# led_frontend.net
KiCad netlist of a schematic drawn in Altium Designer
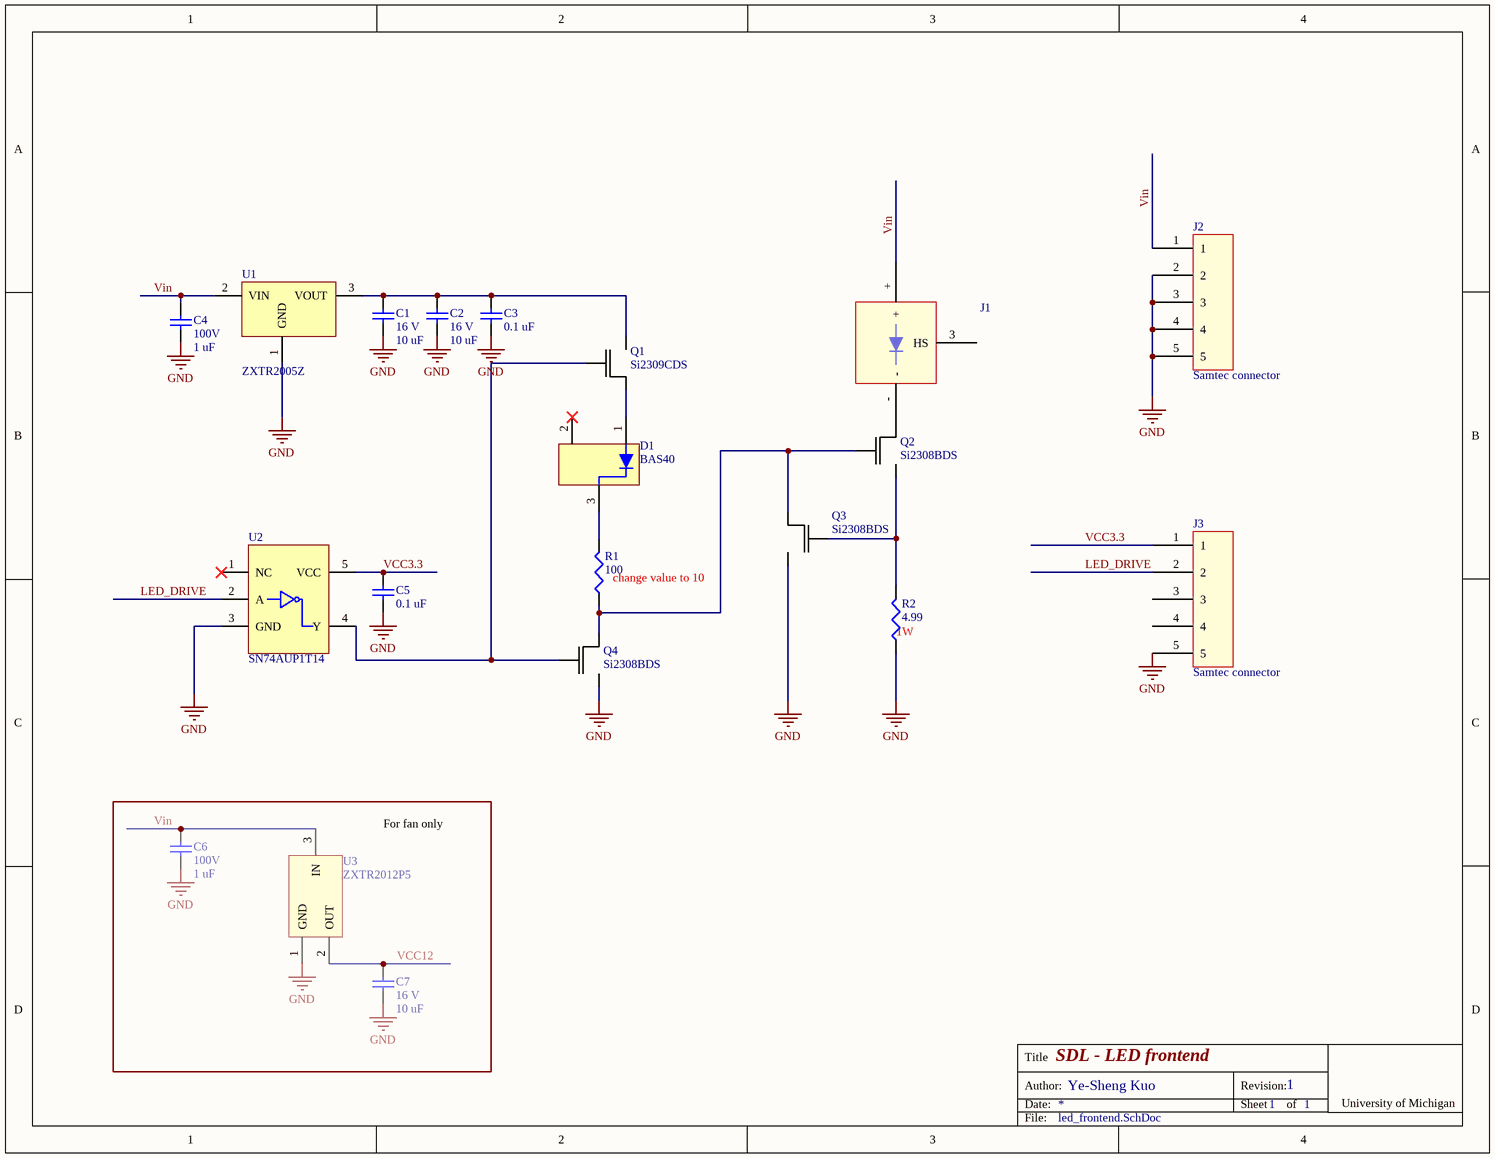
[diagram p0: led_frontend.SchDoc]

(export (version "E")
  (design (tool "Eeschema 10.0.6"))
  (components
    (comp (ref "C1")
      (value "10 uF")
      (footprint "0603")
      (description "Ceramic capacitor, 10 uF, 16 V, 0603 package")
      (fields
        (field (name "TOLERANCE") "20%")
        (field (name "VOLTAGE RATED") "16 V")
        (field (name "Comment") "Ceramic capacitor")
      )
      (libsource (lib "rlc") (part "C_10u_16V_0603_ceramic"))
    )
    (comp (ref "C2")
      (value "10 uF")
      (footprint "0603")
      (description "Ceramic capacitor, 10 uF, 16 V, 0603 package")
      (fields
        (field (name "TOLERANCE") "20%")
        (field (name "VOLTAGE RATED") "16 V")
        (field (name "Comment") "Ceramic capacitor")
      )
      (libsource (lib "rlc") (part "C_10u_16V_0603_ceramic"))
    )
    (comp (ref "C3")
      (value "0.1 uF")
      (footprint "0603")
      (description "Ceramic capacitor, 0.1 uF, 0603 package")
      (fields (field (name "TOLERANCE") "10%") (field (name "Comment") "Ceramic capacitor"))
      (libsource (lib "rlc") (part "C_0.1u_0603_ceramic"))
    )
    (comp (ref "C4")
      (value "1 uF")
      (footprint "0805")
      (description "Ceramic capacitor, 1 uF, 100 V, 0805 package")
      (fields
        (field (name "TOLERANCE") "10%")
        (field (name "VOLTAGE RATED") "100V")
        (field (name "Comment") "Ceramic capacitor")
      )
      (libsource (lib "rlc") (part "C_1u_100V_0805_ceramic"))
    )
    (comp (ref "C5")
      (value "0.1 uF")
      (footprint "0603")
      (description "Ceramic capacitor, 0.1 uF, 0603 package")
      (fields (field (name "TOLERANCE") "10%") (field (name "Comment") "Ceramic capacitor"))
      (libsource (lib "rlc") (part "C_0.1u_0603_ceramic"))
    )
    (comp (ref "C6")
      (value "1 uF")
      (footprint "0805")
      (description "Ceramic capacitor, 1 uF, 100 V, 0805 package")
      (fields
        (field (name "TOLERANCE") "10%")
        (field (name "VOLTAGE RATED") "100V")
        (field (name "Comment") "Ceramic capacitor")
      )
      (libsource (lib "rlc") (part "C_1u_100V_0805_ceramic"))
    )
    (comp (ref "C7")
      (value "10 uF")
      (footprint "0603")
      (description "Ceramic capacitor, 10 uF, 16 V, 0603 package")
      (fields
        (field (name "TOLERANCE") "20%")
        (field (name "VOLTAGE RATED") "16 V")
        (field (name "Comment") "Ceramic capacitor")
      )
      (libsource (lib "rlc") (part "C_10u_16V_0603_ceramic"))
    )
    (comp (ref "D1")
      (value "BAS40")
      (footprint "SOT23-3")
      (description "SURFACE MOUNT SCHOTTKY BARRIER DIODE")
      (libsource (lib "sdl") (part "BAS40"))
    )
    (comp (ref "J1")
      (value "1807200002")
      (footprint "molex")
      (description "LED Array Holders  for CREE* XLamp†   Arrays")
      (libsource (lib "connectors") (part "Molex LED holder"))
    )
    (comp (ref "J2")
      (value "Samtec connector")
      (footprint "TFM-105-02-L-S")
      (description "Samtec connector, 1.27 mm, single row, 5 pos SMD")
      (libsource (lib "connectors") (part "Samtec conntector"))
    )
    (comp (ref "J3")
      (value "Samtec connector")
      (footprint "TFM-105-02-L-S")
      (description "Samtec connector, 1.27 mm, single row, 5 pos SMD")
      (libsource (lib "connectors") (part "Samtec conntector"))
    )
    (comp (ref "Q1")
      (value "Si2309CDS")
      (footprint "SOT23-3")
      (description "P-Channel 60-V (D-S) MOSFET")
      (libsource (lib "transistors") (part "Si2309CDS"))
    )
    (comp (ref "Q2")
      (value "Si2308BDS")
      (footprint "SOT23-3")
      (description "N-Channel 60-V (D-S) MOSFET")
      (libsource (lib "transistors") (part "Si2308BDS"))
    )
    (comp (ref "Q3")
      (value "Si2308BDS")
      (footprint "SOT23-3")
      (description "N-Channel 60-V (D-S) MOSFET")
      (libsource (lib "transistors") (part "Si2308BDS"))
    )
    (comp (ref "Q4")
      (value "Si2308BDS")
      (footprint "SOT23-3")
      (description "N-Channel 60-V (D-S) MOSFET")
      (libsource (lib "transistors") (part "Si2308BDS"))
    )
    (comp (ref "R1")
      (value "100")
      (footprint "0603")
      (description "Chip resistor, 100,  0603 package")
      (fields (field (name "TOLERANCE") "0.1%") (field (name "POWER") "1/1 W"))
      (libsource (lib "rlc") (part "R_100_0603"))
    )
    (comp (ref "R2")
      (value "4.99")
      (footprint "2512")
      (description "Chip resistor, 4.99, 2512 package")
      (fields (field (name "TOLERANCE") "1%") (field (name "POWER") "1 W"))
      (libsource (lib "rlc") (part "R_4.99_2512"))
    )
    (comp (ref "U1")
      (value "ZXTR2005Z")
      (footprint "SOT89")
      (description "100V INPUT, 5V 30mA REGULATOR TRANSISTOR")
      (libsource (lib "ldo") (part "ZXTR2005Z"))
    )
    (comp (ref "U2")
      (value "SN74AUP1T14")
      (footprint "SC-70-5 (DCK)")
      (description "LOW POWER, 1.8/2.5/3.3-V INPUT, 3.3-V CMOS OUTPUT, SINGLE  SCHMITT-TRIGGER INVERTER GATE")
      (libsource (lib "sdl") (part "SN74AUP1T14"))
    )
    (comp (ref "U3")
      (value "ZXTR2012P5")
      (footprint "PowerDI-5")
      (description "100V INPUT, 12V 40mA REGULATOR TRANSISTOR")
      (libsource (lib "ldo") (part "ZXTR2012P5"))
    )
  )
  (nets
    (net (code "1") (name "/LED_DRIVE") (class "Default")
      (node (ref "J3") (pin "2") (pinfunction "2_2") (pintype "passive"))
      (node (ref "U2") (pin "2") (pinfunction "A_2") (pintype "power_in"))
    )
    (net (code "2") (name "/VCC3.3") (class "Default")
      (node (ref "C5") (pin "1") (pintype "passive"))
      (node (ref "J3") (pin "1") (pinfunction "1_1") (pintype "passive"))
      (node (ref "U2") (pin "5") (pinfunction "VCC_5") (pintype "power_in"))
    )
    (net (code "3") (name "/VCC12") (class "Default")
      (node (ref "C7") (pin "1") (pintype "passive"))
      (node (ref "U3") (pin "2") (pinfunction "OUT_2") (pintype "passive"))
    )
    (net (code "4") (name "/Vin") (class "Default")
      (node (ref "C4") (pin "1") (pintype "passive"))
      (node (ref "C6") (pin "1") (pintype "passive"))
      (node (ref "J1") (pin "+") (pinfunction "+_+") (pintype "passive"))
      (node (ref "J2") (pin "1") (pinfunction "1_1") (pintype "passive"))
      (node (ref "U1") (pin "2") (pinfunction "VIN_2") (pintype "passive"))
      (node (ref "U3") (pin "3") (pinfunction "IN_3") (pintype "passive"))
    )
    (net (code "5") (name "GND") (class "Default")
      (node (ref "C1") (pin "2") (pintype "passive"))
      (node (ref "C2") (pin "2") (pintype "passive"))
      (node (ref "C3") (pin "2") (pintype "passive"))
      (node (ref "C4") (pin "2") (pintype "passive"))
      (node (ref "C5") (pin "2") (pintype "passive"))
      (node (ref "C6") (pin "2") (pintype "passive"))
      (node (ref "C7") (pin "2") (pintype "passive"))
      (node (ref "J2") (pin "2") (pinfunction "2_2") (pintype "passive"))
      (node (ref "J2") (pin "3") (pinfunction "3_3") (pintype "passive"))
      (node (ref "J2") (pin "4") (pinfunction "4_4") (pintype "passive"))
      (node (ref "J2") (pin "5") (pinfunction "5_5") (pintype "passive"))
      (node (ref "J3") (pin "5") (pinfunction "5_5") (pintype "passive"))
      (node (ref "Q3") (pin "2") (pinfunction "S_2") (pintype "passive"))
      (node (ref "Q4") (pin "2") (pinfunction "S_2") (pintype "passive"))
      (node (ref "R2") (pin "2") (pintype "passive"))
      (node (ref "U1") (pin "1") (pinfunction "GND_1") (pintype "passive"))
      (node (ref "U2") (pin "3") (pinfunction "GND_3") (pintype "power_in"))
      (node (ref "U3") (pin "1") (pinfunction "GND_1") (pintype "passive"))
    )
    (net (code "6") (name "Net-(D1-Pad3)") (class "Default")
      (node (ref "D1") (pin "3") (pinfunction "3_3") (pintype "passive"))
      (node (ref "R1") (pin "1") (pintype "passive"))
    )
    (net (code "7") (name "Net-(Q1-D)") (class "Default")
      (node (ref "D1") (pin "1") (pinfunction "1_1") (pintype "passive"))
      (node (ref "Q1") (pin "3") (pinfunction "D_3") (pintype "passive"))
    )
    (net (code "8") (name "Net-(Q1-G)") (class "Default")
      (node (ref "Q1") (pin "1") (pinfunction "G_1") (pintype "passive"))
      (node (ref "Q4") (pin "1") (pinfunction "G_1") (pintype "passive"))
      (node (ref "U2") (pin "4") (pinfunction "Y_4") (pintype "power_in"))
    )
    (net (code "9") (name "Net-(Q1-S)") (class "Default")
      (node (ref "C1") (pin "1") (pintype "passive"))
      (node (ref "C2") (pin "1") (pintype "passive"))
      (node (ref "C3") (pin "1") (pintype "passive"))
      (node (ref "Q1") (pin "2") (pinfunction "S_2") (pintype "passive"))
      (node (ref "U1") (pin "3") (pinfunction "VOUT_3") (pintype "passive"))
    )
    (net (code "10") (name "Net-(Q2-D)") (class "Default")
      (node (ref "J1") (pin "-") (pinfunction "-_-") (pintype "passive"))
      (node (ref "Q2") (pin "3") (pinfunction "D_3") (pintype "passive"))
    )
    (net (code "11") (name "Net-(Q2-G)") (class "Default")
      (node (ref "Q2") (pin "1") (pinfunction "G_1") (pintype "passive"))
      (node (ref "Q3") (pin "3") (pinfunction "D_3") (pintype "passive"))
      (node (ref "Q4") (pin "3") (pinfunction "D_3") (pintype "passive"))
      (node (ref "R1") (pin "2") (pintype "passive"))
    )
    (net (code "12") (name "Net-(Q2-S)") (class "Default")
      (node (ref "Q2") (pin "2") (pinfunction "S_2") (pintype "passive"))
      (node (ref "Q3") (pin "1") (pinfunction "G_1") (pintype "passive"))
      (node (ref "R2") (pin "1") (pintype "passive"))
    )
    (net (code "13") (name "unconnected-(D1-Pad2)") (class "Default")
      (node (ref "D1") (pin "2") (pinfunction "2_2") (pintype "passive+no_connect"))
    )
    (net (code "14") (name "unconnected-(J1-HS-Pad3)") (class "Default")
      (node (ref "J1") (pin "3") (pinfunction "HS_3") (pintype "passive"))
    )
    (net (code "15") (name "unconnected-(J3-Pad3)") (class "Default")
      (node (ref "J3") (pin "3") (pinfunction "3_3") (pintype "passive"))
    )
    (net (code "16") (name "unconnected-(J3-Pad4)") (class "Default")
      (node (ref "J3") (pin "4") (pinfunction "4_4") (pintype "passive"))
    )
    (net (code "17") (name "unconnected-(U2-NC-Pad1)") (class "Default")
      (node (ref "U2") (pin "1") (pinfunction "NC_1") (pintype "power_in+no_connect"))
    )
  )
)
